# Sheet_1_2022-03-11.net
KiCad netlist of a schematic drawn in Altium Designer
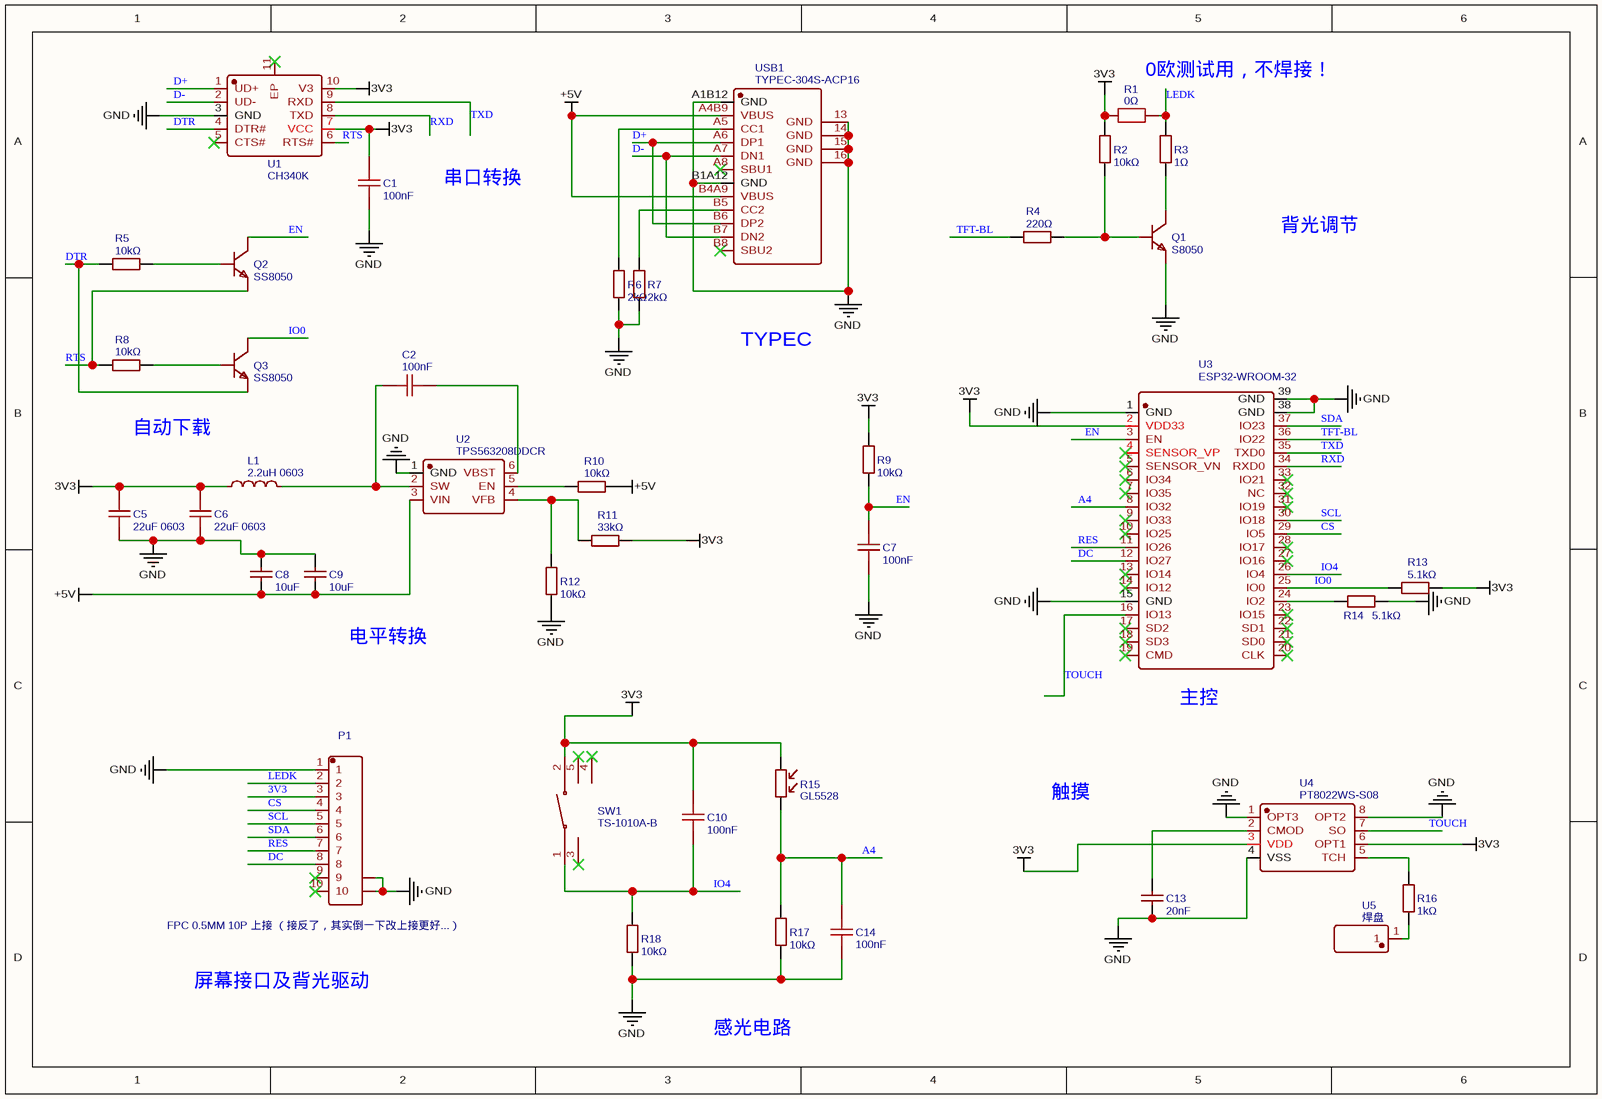
[diagram p0: Sheet_1_2022-03-11.schdoc]

(export (version "E")
  (design (tool "Eeschema 10.0.6"))
  (components
    (comp (ref "C1")
      (value "100nF")
      (fields
        (field (name "BOM_SUPPLIER PART") "C307331")
        (field (name "BOM_MANUFACTURER PART") "CL05B104KB54PNC")
        (field (name "CONTRIBUTOR") "LCSC")
      )
      (libsource (lib "altium-import") (part "root_1_100nF_"))
    )
    (comp (ref "C2")
      (value "100nF")
      (fields
        (field (name "BOM_SUPPLIER PART") "C307331")
        (field (name "BOM_MANUFACTURER PART") "CL05B104KB54PNC")
        (field (name "CONTRIBUTOR") "LCSC")
      )
      (libsource (lib "altium-import") (part "root_2_100nF_"))
    )
    (comp (ref "C5")
      (value "22uF 0603")
      (fields (field (name "CONTRIBUTOR") "LCEDA_Lib"))
      (libsource (lib "altium-import") (part "root_1_22uF 0603_"))
    )
    (comp (ref "C6")
      (value "22uF 0603")
      (fields (field (name "CONTRIBUTOR") "LCEDA_Lib"))
      (libsource (lib "altium-import") (part "root_1_22uF 0603_"))
    )
    (comp (ref "C7")
      (value "100nF")
      (fields
        (field (name "BOM_SUPPLIER PART") "C307331")
        (field (name "BOM_MANUFACTURER PART") "CL05B104KB54PNC")
        (field (name "CONTRIBUTOR") "LCSC")
      )
      (libsource (lib "altium-import") (part "root_1_100nF_"))
    )
    (comp (ref "C8")
      (value "10uF")
      (fields
        (field (name "BOM_MANUFACTURER PART") "CL05A106MQ5NUNC")
        (field (name "BOM_SUPPLIER PART") "C15525")
      )
      (libsource (lib "altium-import") (part "root_1_10uF_"))
    )
    (comp (ref "C9")
      (value "10uF")
      (fields
        (field (name "BOM_MANUFACTURER PART") "CL05A106MQ5NUNC")
        (field (name "BOM_SUPPLIER PART") "C15525")
      )
      (libsource (lib "altium-import") (part "root_1_10uF_"))
    )
    (comp (ref "C10")
      (value "100nF")
      (fields
        (field (name "BOM_SUPPLIER PART") "C307331")
        (field (name "BOM_MANUFACTURER PART") "CL05B104KB54PNC")
        (field (name "CONTRIBUTOR") "LCSC")
      )
      (libsource (lib "altium-import") (part "root_1_100nF_"))
    )
    (comp (ref "C13")
      (value "20nF")
      (fields
        (field (name "BOM_MANUFACTURER PART") "0402F203M500NT")
        (field (name "BOM_SUPPLIER PART") "C79469")
      )
      (libsource (lib "altium-import") (part "root_3_20nF_"))
    )
    (comp (ref "C14")
      (value "100nF")
      (fields
        (field (name "BOM_SUPPLIER PART") "C307331")
        (field (name "BOM_MANUFACTURER PART") "CL05B104KB54PNC")
        (field (name "CONTRIBUTOR") "LCSC")
      )
      (libsource (lib "altium-import") (part "root_1_100nF_"))
    )
    (comp (ref "L1")
      (value "2.2uH 0603")
      (fields (field (name "CONTRIBUTOR") "LCEDA_Lib"))
      (libsource (lib "altium-import") (part "root_0_2.2uH 0603_"))
    )
    (comp (ref "P1")
      (value "FPC 0.5MM 10P 上接 （接反了，其实倒一下改上接更好...）")
      (fields
        (field (name "BOM_MANUFACTURER PART") "FPC 0.5MM 10P Pull type H2.0mm Pick up")
        (field (name "BOM_SUPPLIER PART") "C11085")
      )
      (libsource (lib "altium-import") (part "root_0_FPC 0.5MM 10P 上接 （接反了，其实倒一下改上接更好...）_"))
    )
    (comp (ref "Q1")
      (value "S8050")
      (fields (field (name "BOM_SUPPLIER PART") "C916390") (field (name "CONTRIBUTOR") "LCSC"))
      (libsource (lib "altium-import") (part "root_0_S8050_"))
    )
    (comp (ref "Q2")
      (value "SS8050")
      (fields (field (name "BOM_SUPPLIER PART") "C2688219") (field (name "CONTRIBUTOR") "LCSC"))
      (libsource (lib "altium-import") (part "root_0_SS8050_"))
    )
    (comp (ref "Q3")
      (value "SS8050")
      (fields (field (name "BOM_SUPPLIER PART") "C2688219") (field (name "CONTRIBUTOR") "LCSC"))
      (libsource (lib "altium-import") (part "root_0_SS8050_"))
    )
    (comp (ref "R1")
      (value "0Ω")
      (fields (field (name "CONTRIBUTOR") "LCEDA_Lib"))
      (libsource (lib "altium-import") (part "root_0_0Ω_"))
    )
    (comp (ref "R2")
      (value "10kΩ")
      (fields
        (field (name "BOM_MANUFACTURER PART") "0402WGF1002TCE")
        (field (name "BOM_SUPPLIER PART") "C25744")
      )
      (libsource (lib "altium-import") (part "root_1_10kΩ_"))
    )
    (comp (ref "R3")
      (value "1Ω")
      (fields
        (field (name "BOM_MANUFACTURER PART") "0402WGF100KTCE")
        (field (name "BOM_SUPPLIER PART") "C25086")
      )
      (libsource (lib "altium-import") (part "root_1_1Ω_"))
    )
    (comp (ref "R4")
      (value "220Ω")
      (fields
        (field (name "BOM_MANUFACTURER PART") "0603WAF2200T5E")
        (field (name "BOM_SUPPLIER PART") "C22962")
      )
      (libsource (lib "altium-import") (part "root_2_220Ω_"))
    )
    (comp (ref "R5")
      (value "10kΩ")
      (fields
        (field (name "BOM_MANUFACTURER PART") "0402WGF1002TCE")
        (field (name "BOM_SUPPLIER PART") "C25744")
      )
      (libsource (lib "altium-import") (part "root_0_10kΩ_"))
    )
    (comp (ref "R6")
      (value "2kΩ")
      (fields
        (field (name "BOM_MANUFACTURER PART") "0402WGF2001TCE")
        (field (name "BOM_SUPPLIER PART") "C4109")
      )
      (libsource (lib "altium-import") (part "root_1_2kΩ_"))
    )
    (comp (ref "R7")
      (value "2kΩ")
      (fields
        (field (name "BOM_MANUFACTURER PART") "0402WGF2001TCE")
        (field (name "BOM_SUPPLIER PART") "C4109")
      )
      (libsource (lib "altium-import") (part "root_1_2kΩ_"))
    )
    (comp (ref "R8")
      (value "10kΩ")
      (fields
        (field (name "BOM_MANUFACTURER PART") "0402WGF1002TCE")
        (field (name "BOM_SUPPLIER PART") "C25744")
      )
      (libsource (lib "altium-import") (part "root_2_10kΩ_"))
    )
    (comp (ref "R9")
      (value "10kΩ")
      (fields
        (field (name "BOM_MANUFACTURER PART") "0402WGF1002TCE")
        (field (name "BOM_SUPPLIER PART") "C25744")
      )
      (libsource (lib "altium-import") (part "root_1_10kΩ_"))
    )
    (comp (ref "R10")
      (value "10kΩ")
      (fields
        (field (name "BOM_MANUFACTURER PART") "0402WGF1002TCE")
        (field (name "BOM_SUPPLIER PART") "C25744")
      )
      (libsource (lib "altium-import") (part "root_0_10kΩ_"))
    )
    (comp (ref "R11")
      (value "33kΩ")
      (fields
        (field (name "BOM_MANUFACTURER PART") "0402WGF3302TCE")
        (field (name "BOM_SUPPLIER PART") "C25779")
      )
      (libsource (lib "altium-import") (part "root_0_33kΩ_"))
    )
    (comp (ref "R12")
      (value "10kΩ")
      (fields
        (field (name "BOM_MANUFACTURER PART") "0402WGF1002TCE")
        (field (name "BOM_SUPPLIER PART") "C25744")
      )
      (libsource (lib "altium-import") (part "root_1_10kΩ_"))
    )
    (comp (ref "R13")
      (value "5.1kΩ")
      (fields
        (field (name "BOM_MANUFACTURER PART") "0402WGF5101TCE")
        (field (name "BOM_SUPPLIER PART") "C25905")
      )
      (libsource (lib "altium-import") (part "root_0_5.1kΩ_"))
    )
    (comp (ref "R14")
      (value "5.1kΩ")
      (fields
        (field (name "BOM_MANUFACTURER PART") "0402WGF5101TCE")
        (field (name "BOM_SUPPLIER PART") "C25905")
      )
      (libsource (lib "altium-import") (part "root_0_5.1kΩ_"))
    )
    (comp (ref "R15")
      (value "GL5528")
      (fields (field (name "BOM_SUPPLIER PART") "C125627"))
      (libsource (lib "altium-import") (part "root_3_GL5528_"))
    )
    (comp (ref "R16")
      (value "1kΩ")
      (fields
        (field (name "BOM_MANUFACTURER PART") "0402WGF1001TCE")
        (field (name "BOM_SUPPLIER PART") "C11702")
      )
      (libsource (lib "altium-import") (part "root_1_1kΩ_"))
    )
    (comp (ref "R17")
      (value "10kΩ")
      (fields
        (field (name "BOM_MANUFACTURER PART") "0402WGF1002TCE")
        (field (name "BOM_SUPPLIER PART") "C25744")
      )
      (libsource (lib "altium-import") (part "root_1_10kΩ_"))
    )
    (comp (ref "R18")
      (value "10kΩ")
      (fields
        (field (name "BOM_MANUFACTURER PART") "0402WGF1002TCE")
        (field (name "BOM_SUPPLIER PART") "C25744")
      )
      (libsource (lib "altium-import") (part "root_1_10kΩ_"))
    )
    (comp (ref "SW1")
      (value "TS-1010A-B")
      (fields (field (name "BOM_SUPPLIER PART") "C381059") (field (name "CONTRIBUTOR") "LCSC"))
      (libsource (lib "altium-import") (part "root_1_TS-1010A-B_"))
    )
    (comp (ref "U1")
      (value "CH340K")
      (fields (field (name "BOM_SUPPLIER PART") "C968586") (field (name "CONTRIBUTOR") "LCSC"))
      (libsource (lib "altium-import") (part "root_0_CH340K_"))
    )
    (comp (ref "U2")
      (value "TPS563208DDCR")
      (fields (field (name "BOM_SUPPLIER PART") "C468250") (field (name "CONTRIBUTOR") "LCSC"))
      (libsource (lib "altium-import") (part "root_0_TPS563208DDCR_"))
    )
    (comp (ref "U3")
      (value "ESP32-WROOM-32")
      (fields (field (name "BOM_SUPPLIER PART") "C503587") (field (name "CONTRIBUTOR") "LCSC"))
      (libsource (lib "altium-import") (part "root_0_ESP32-WROOM-32_"))
    )
    (comp (ref "U4")
      (value "PT8022WS-S08")
      (fields (field (name "BOM_SUPPLIER PART") "C2936083") (field (name "CONTRIBUTOR") "LCSC"))
      (libsource (lib "altium-import") (part "root_0_PT8022WS-S08_"))
    )
    (comp (ref "U5")
      (value "焊盘")
      (fields (field (name "BOM_MANUFACTURER PART") "New SchematicLib") (field (name "CONTRIBUTOR") "Kisro"))
      (libsource (lib "altium-import") (part "root_2_焊盘_"))
    )
    (comp (ref "USB1")
      (value "TYPEC-304S-ACP16")
      (fields (field (name "BOM_SUPPLIER PART") "C720630") (field (name "CONTRIBUTOR") "LCSC"))
      (libsource (lib "altium-import") (part "root_0_TYPEC-304S-ACP16_"))
    )
  )
  (nets
    (net (code "1") (name "+5V") (class "Default")
      (node (ref "C8") (pin "1") (pinfunction "1_1") (pintype "passive"))
      (node (ref "C9") (pin "1") (pinfunction "1_1") (pintype "passive"))
      (node (ref "R10") (pin "2") (pinfunction "2_2") (pintype "passive"))
      (node (ref "U2") (pin "3") (pinfunction "VIN_3") (pintype "passive"))
      (node (ref "USB1") (pin "A4B9") (pinfunction "VBUS_A4B9") (pintype "passive"))
      (node (ref "USB1") (pin "B4A9") (pinfunction "VBUS_B4A9") (pintype "passive"))
    )
    (net (code "2") (name "/A4") (class "Default")
      (node (ref "C14") (pin "2") (pinfunction "2_2") (pintype "passive"))
      (node (ref "R15") (pin "2") (pinfunction "2_2") (pintype "passive"))
      (node (ref "R17") (pin "2") (pinfunction "2_2") (pintype "passive"))
      (node (ref "U3") (pin "8") (pinfunction "IO32_8") (pintype "passive"))
    )
    (net (code "3") (name "/CS") (class "Default")
      (node (ref "P1") (pin "4") (pinfunction "4_4") (pintype "passive"))
      (node (ref "U3") (pin "29") (pinfunction "IO5_29") (pintype "passive"))
    )
    (net (code "4") (name "/D+") (class "Default")
      (node (ref "U1") (pin "1") (pinfunction "UD+_1") (pintype "passive"))
      (node (ref "USB1") (pin "A6") (pinfunction "DP1_A6") (pintype "passive"))
      (node (ref "USB1") (pin "B6") (pinfunction "DP2_B6") (pintype "passive"))
    )
    (net (code "5") (name "/D-") (class "Default")
      (node (ref "U1") (pin "2") (pinfunction "UD-_2") (pintype "passive"))
      (node (ref "USB1") (pin "A7") (pinfunction "DN1_A7") (pintype "passive"))
      (node (ref "USB1") (pin "B7") (pinfunction "DN2_B7") (pintype "passive"))
    )
    (net (code "6") (name "/DC") (class "Default")
      (node (ref "P1") (pin "8") (pinfunction "8_8") (pintype "passive"))
      (node (ref "U3") (pin "12") (pinfunction "IO27_12") (pintype "passive"))
    )
    (net (code "7") (name "/DTR") (class "Default")
      (node (ref "Q3") (pin "2") (pinfunction "E_2") (pintype "passive"))
      (node (ref "R5") (pin "1") (pinfunction "1_1") (pintype "passive"))
      (node (ref "U1") (pin "4") (pinfunction "DTR#_4") (pintype "passive"))
    )
    (net (code "8") (name "/EN") (class "Default")
      (node (ref "C7") (pin "2") (pinfunction "2_2") (pintype "passive"))
      (node (ref "Q2") (pin "3") (pinfunction "C_3") (pintype "passive"))
      (node (ref "R9") (pin "1") (pinfunction "1_1") (pintype "passive"))
      (node (ref "U3") (pin "3") (pinfunction "EN_3") (pintype "passive"))
    )
    (net (code "9") (name "/IO0") (class "Default")
      (node (ref "Q3") (pin "3") (pinfunction "C_3") (pintype "passive"))
      (node (ref "R13") (pin "1") (pinfunction "1_1") (pintype "passive"))
      (node (ref "U3") (pin "25") (pinfunction "IO0_25") (pintype "passive"))
    )
    (net (code "10") (name "/IO4") (class "Default")
      (node (ref "C10") (pin "1") (pinfunction "1_1") (pintype "passive"))
      (node (ref "R18") (pin "2") (pinfunction "2_2") (pintype "passive"))
      (node (ref "SW1") (pin "1") (pinfunction "1_1") (pintype "passive"))
      (node (ref "U3") (pin "26") (pinfunction "IO4_26") (pintype "passive"))
    )
    (net (code "11") (name "/LEDK") (class "Default")
      (node (ref "P1") (pin "2") (pinfunction "2_2") (pintype "passive"))
      (node (ref "R1") (pin "2") (pinfunction "2_2") (pintype "passive"))
      (node (ref "R3") (pin "2") (pinfunction "2_2") (pintype "passive"))
    )
    (net (code "12") (name "/RES") (class "Default")
      (node (ref "P1") (pin "7") (pinfunction "7_7") (pintype "passive"))
      (node (ref "U3") (pin "11") (pinfunction "IO26_11") (pintype "passive"))
    )
    (net (code "13") (name "/RTS") (class "Default")
      (node (ref "Q2") (pin "2") (pinfunction "E_2") (pintype "passive"))
      (node (ref "R8") (pin "2") (pinfunction "2_2") (pintype "passive"))
      (node (ref "U1") (pin "6") (pinfunction "RTS#_6") (pintype "passive"))
    )
    (net (code "14") (name "/RXD") (class "Default")
      (node (ref "U1") (pin "8") (pinfunction "TXD_8") (pintype "passive"))
      (node (ref "U3") (pin "34") (pinfunction "RXD0_34") (pintype "passive"))
    )
    (net (code "15") (name "/SCL") (class "Default")
      (node (ref "P1") (pin "5") (pinfunction "5_5") (pintype "passive"))
      (node (ref "U3") (pin "30") (pinfunction "IO18_30") (pintype "passive"))
    )
    (net (code "16") (name "/SDA") (class "Default")
      (node (ref "P1") (pin "6") (pinfunction "6_6") (pintype "passive"))
      (node (ref "U3") (pin "37") (pinfunction "IO23_37") (pintype "passive"))
    )
    (net (code "17") (name "/TFT-BL") (class "Default")
      (node (ref "R4") (pin "2") (pinfunction "2_2") (pintype "passive"))
      (node (ref "U3") (pin "36") (pinfunction "IO22_36") (pintype "passive"))
    )
    (net (code "18") (name "/TOUCH") (class "Default")
      (node (ref "U3") (pin "16") (pinfunction "IO13_16") (pintype "passive"))
      (node (ref "U4") (pin "7") (pinfunction "SO_7") (pintype "passive"))
    )
    (net (code "19") (name "/TXD") (class "Default")
      (node (ref "U1") (pin "9") (pinfunction "RXD_9") (pintype "passive"))
      (node (ref "U3") (pin "35") (pinfunction "TXD0_35") (pintype "passive"))
    )
    (net (code "20") (name "3V3") (class "Default")
      (node (ref "C1") (pin "2") (pinfunction "2_2") (pintype "passive"))
      (node (ref "C10") (pin "2") (pinfunction "2_2") (pintype "passive"))
      (node (ref "C5") (pin "2") (pinfunction "2_2") (pintype "passive"))
      (node (ref "C6") (pin "2") (pinfunction "2_2") (pintype "passive"))
      (node (ref "L1") (pin "1") (pinfunction "1_1") (pintype "passive"))
      (node (ref "P1") (pin "3") (pinfunction "3_3") (pintype "passive"))
      (node (ref "R1") (pin "1") (pinfunction "1_1") (pintype "passive"))
      (node (ref "R11") (pin "2") (pinfunction "2_2") (pintype "passive"))
      (node (ref "R13") (pin "2") (pinfunction "2_2") (pintype "passive"))
      (node (ref "R15") (pin "1") (pinfunction "1_1") (pintype "passive"))
      (node (ref "R2") (pin "2") (pinfunction "2_2") (pintype "passive"))
      (node (ref "R9") (pin "2") (pinfunction "2_2") (pintype "passive"))
      (node (ref "SW1") (pin "2") (pinfunction "2_2") (pintype "passive"))
      (node (ref "U1") (pin "10") (pinfunction "V3_10") (pintype "passive"))
      (node (ref "U1") (pin "7") (pinfunction "VCC_7") (pintype "passive"))
      (node (ref "U3") (pin "2") (pinfunction "VDD33_2") (pintype "passive"))
      (node (ref "U4") (pin "3") (pinfunction "VDD_3") (pintype "passive"))
      (node (ref "U4") (pin "6") (pinfunction "OPT1_6") (pintype "passive"))
    )
    (net (code "21") (name "GND") (class "Default")
      (node (ref "C1") (pin "1") (pinfunction "1_1") (pintype "passive"))
      (node (ref "C13") (pin "2") (pinfunction "2_2") (pintype "passive"))
      (node (ref "C14") (pin "1") (pinfunction "1_1") (pintype "passive"))
      (node (ref "C5") (pin "1") (pinfunction "1_1") (pintype "passive"))
      (node (ref "C6") (pin "1") (pinfunction "1_1") (pintype "passive"))
      (node (ref "C7") (pin "1") (pinfunction "1_1") (pintype "passive"))
      (node (ref "C8") (pin "2") (pinfunction "2_2") (pintype "passive"))
      (node (ref "C9") (pin "2") (pinfunction "2_2") (pintype "passive"))
      (node (ref "P1") (pin "1") (pinfunction "1_1") (pintype "passive"))
      (node (ref "P1") (pin "11") (pinfunction "11_11") (pintype "passive"))
      (node (ref "P1") (pin "12") (pinfunction "12_12") (pintype "passive"))
      (node (ref "Q1") (pin "2") (pinfunction "E_2") (pintype "passive"))
      (node (ref "R12") (pin "1") (pinfunction "1_1") (pintype "passive"))
      (node (ref "R14") (pin "2") (pinfunction "2_2") (pintype "passive"))
      (node (ref "R17") (pin "1") (pinfunction "1_1") (pintype "passive"))
      (node (ref "R18") (pin "1") (pinfunction "1_1") (pintype "passive"))
      (node (ref "R6") (pin "1") (pinfunction "1_1") (pintype "passive"))
      (node (ref "R7") (pin "1") (pinfunction "1_1") (pintype "passive"))
      (node (ref "U1") (pin "3") (pinfunction "GND_3") (pintype "passive"))
      (node (ref "U2") (pin "1") (pinfunction "GND_1") (pintype "passive"))
      (node (ref "U3") (pin "1") (pinfunction "GND_1") (pintype "passive"))
      (node (ref "U3") (pin "15") (pinfunction "GND_15") (pintype "passive"))
      (node (ref "U3") (pin "38") (pinfunction "GND_38") (pintype "passive"))
      (node (ref "U3") (pin "39") (pinfunction "GND_39") (pintype "passive"))
      (node (ref "U4") (pin "1") (pinfunction "OPT3_1") (pintype "passive"))
      (node (ref "U4") (pin "4") (pinfunction "VSS_4") (pintype "passive"))
      (node (ref "U4") (pin "8") (pinfunction "OPT2_8") (pintype "passive"))
      (node (ref "USB1") (pin "13") (pinfunction "GND_13") (pintype "passive"))
      (node (ref "USB1") (pin "14") (pinfunction "GND_14") (pintype "passive"))
      (node (ref "USB1") (pin "15") (pinfunction "GND_15") (pintype "passive"))
      (node (ref "USB1") (pin "16") (pinfunction "GND_16") (pintype "passive"))
      (node (ref "USB1") (pin "A1B12") (pinfunction "GND_A1B12") (pintype "passive"))
      (node (ref "USB1") (pin "B1A12") (pinfunction "GND_B1A12") (pintype "passive"))
    )
    (net (code "22") (name "Net-(Q1-B)") (class "Default")
      (node (ref "Q1") (pin "1") (pinfunction "B_1") (pintype "passive"))
      (node (ref "R2") (pin "1") (pinfunction "1_1") (pintype "passive"))
      (node (ref "R4") (pin "1") (pinfunction "1_1") (pintype "passive"))
    )
    (net (code "23") (name "Net-(Q1-C)") (class "Default")
      (node (ref "Q1") (pin "3") (pinfunction "C_3") (pintype "passive"))
      (node (ref "R3") (pin "1") (pinfunction "1_1") (pintype "passive"))
    )
    (net (code "24") (name "Net-(Q2-B)") (class "Default")
      (node (ref "Q2") (pin "1") (pinfunction "B_1") (pintype "passive"))
      (node (ref "R5") (pin "2") (pinfunction "2_2") (pintype "passive"))
    )
    (net (code "25") (name "Net-(Q3-B)") (class "Default")
      (node (ref "Q3") (pin "1") (pinfunction "B_1") (pintype "passive"))
      (node (ref "R8") (pin "1") (pinfunction "1_1") (pintype "passive"))
    )
    (net (code "26") (name "Net-(R16-Pad1)") (class "Default")
      (node (ref "R16") (pin "1") (pinfunction "1_1") (pintype "passive"))
      (node (ref "U5") (pin "1") (pinfunction "1_1") (pintype "passive"))
    )
    (net (code "27") (name "Net-(U2-EN)") (class "Default")
      (node (ref "R10") (pin "1") (pinfunction "1_1") (pintype "passive"))
      (node (ref "U2") (pin "5") (pinfunction "EN_5") (pintype "passive"))
    )
    (net (code "28") (name "Net-(U2-SW)") (class "Default")
      (node (ref "C2") (pin "2") (pinfunction "2_2") (pintype "passive"))
      (node (ref "L1") (pin "2") (pinfunction "2_2") (pintype "passive"))
      (node (ref "U2") (pin "2") (pinfunction "SW_2") (pintype "passive"))
    )
    (net (code "29") (name "Net-(U2-VBST)") (class "Default")
      (node (ref "C2") (pin "1") (pinfunction "1_1") (pintype "passive"))
      (node (ref "U2") (pin "6") (pinfunction "VBST_6") (pintype "passive"))
    )
    (net (code "30") (name "Net-(U2-VFB)") (class "Default")
      (node (ref "R11") (pin "1") (pinfunction "1_1") (pintype "passive"))
      (node (ref "R12") (pin "2") (pinfunction "2_2") (pintype "passive"))
      (node (ref "U2") (pin "4") (pinfunction "VFB_4") (pintype "passive"))
    )
    (net (code "31") (name "Net-(U3-IO2)") (class "Default")
      (node (ref "R14") (pin "1") (pinfunction "1_1") (pintype "passive"))
      (node (ref "U3") (pin "24") (pinfunction "IO2_24") (pintype "passive"))
    )
    (net (code "32") (name "Net-(U4-CMOD)") (class "Default")
      (node (ref "C13") (pin "1") (pinfunction "1_1") (pintype "passive"))
      (node (ref "U4") (pin "2") (pinfunction "CMOD_2") (pintype "passive"))
    )
    (net (code "33") (name "Net-(U4-TCH)") (class "Default")
      (node (ref "R16") (pin "2") (pinfunction "2_2") (pintype "passive"))
      (node (ref "U4") (pin "5") (pinfunction "TCH_5") (pintype "passive"))
    )
    (net (code "34") (name "Net-(USB1-CC1)") (class "Default")
      (node (ref "R6") (pin "2") (pinfunction "2_2") (pintype "passive"))
      (node (ref "USB1") (pin "A5") (pinfunction "CC1_A5") (pintype "passive"))
    )
    (net (code "35") (name "Net-(USB1-CC2)") (class "Default")
      (node (ref "R7") (pin "2") (pinfunction "2_2") (pintype "passive"))
      (node (ref "USB1") (pin "B5") (pinfunction "CC2_B5") (pintype "passive"))
    )
    (net (code "36") (name "unconnected-(P1-Pad9)") (class "Default")
      (node (ref "P1") (pin "9") (pinfunction "9_9") (pintype "passive+no_connect"))
    )
    (net (code "37") (name "unconnected-(P1-Pad10)") (class "Default")
      (node (ref "P1") (pin "10") (pinfunction "10_10") (pintype "passive+no_connect"))
    )
    (net (code "38") (name "unconnected-(SW1-Pad3)") (class "Default")
      (node (ref "SW1") (pin "3") (pinfunction "3_3") (pintype "passive+no_connect"))
    )
    (net (code "39") (name "unconnected-(SW1-Pad4)") (class "Default")
      (node (ref "SW1") (pin "4") (pinfunction "4_4") (pintype "passive+no_connect"))
    )
    (net (code "40") (name "unconnected-(SW1-Pad5)") (class "Default")
      (node (ref "SW1") (pin "5") (pinfunction "5_5") (pintype "passive+no_connect"))
    )
    (net (code "41") (name "unconnected-(U1-CTS#-Pad5)") (class "Default")
      (node (ref "U1") (pin "5") (pinfunction "CTS#_5") (pintype "passive+no_connect"))
    )
    (net (code "42") (name "unconnected-(U1-EP-Pad11)") (class "Default")
      (node (ref "U1") (pin "11") (pinfunction "EP_11") (pintype "passive+no_connect"))
    )
    (net (code "43") (name "unconnected-(U3-CLK-Pad20)") (class "Default")
      (node (ref "U3") (pin "20") (pinfunction "CLK_20") (pintype "passive+no_connect"))
    )
    (net (code "44") (name "unconnected-(U3-CMD-Pad19)") (class "Default")
      (node (ref "U3") (pin "19") (pinfunction "CMD_19") (pintype "passive+no_connect"))
    )
    (net (code "45") (name "unconnected-(U3-IO12-Pad14)") (class "Default")
      (node (ref "U3") (pin "14") (pinfunction "IO12_14") (pintype "passive+no_connect"))
    )
    (net (code "46") (name "unconnected-(U3-IO14-Pad13)") (class "Default")
      (node (ref "U3") (pin "13") (pinfunction "IO14_13") (pintype "passive+no_connect"))
    )
    (net (code "47") (name "unconnected-(U3-IO15-Pad23)") (class "Default")
      (node (ref "U3") (pin "23") (pinfunction "IO15_23") (pintype "passive+no_connect"))
    )
    (net (code "48") (name "unconnected-(U3-IO16-Pad27)") (class "Default")
      (node (ref "U3") (pin "27") (pinfunction "IO16_27") (pintype "passive+no_connect"))
    )
    (net (code "49") (name "unconnected-(U3-IO17-Pad28)") (class "Default")
      (node (ref "U3") (pin "28") (pinfunction "IO17_28") (pintype "passive+no_connect"))
    )
    (net (code "50") (name "unconnected-(U3-IO19-Pad31)") (class "Default")
      (node (ref "U3") (pin "31") (pinfunction "IO19_31") (pintype "passive+no_connect"))
    )
    (net (code "51") (name "unconnected-(U3-IO21-Pad33)") (class "Default")
      (node (ref "U3") (pin "33") (pinfunction "IO21_33") (pintype "passive+no_connect"))
    )
    (net (code "52") (name "unconnected-(U3-IO25-Pad10)") (class "Default")
      (node (ref "U3") (pin "10") (pinfunction "IO25_10") (pintype "passive+no_connect"))
    )
    (net (code "53") (name "unconnected-(U3-IO33-Pad9)") (class "Default")
      (node (ref "U3") (pin "9") (pinfunction "IO33_9") (pintype "passive+no_connect"))
    )
    (net (code "54") (name "unconnected-(U3-IO34-Pad6)") (class "Default")
      (node (ref "U3") (pin "6") (pinfunction "IO34_6") (pintype "passive+no_connect"))
    )
    (net (code "55") (name "unconnected-(U3-IO35-Pad7)") (class "Default")
      (node (ref "U3") (pin "7") (pinfunction "IO35_7") (pintype "passive+no_connect"))
    )
    (net (code "56") (name "unconnected-(U3-NC-Pad32)") (class "Default")
      (node (ref "U3") (pin "32") (pinfunction "NC_32") (pintype "passive+no_connect"))
    )
    (net (code "57") (name "unconnected-(U3-SD0-Pad21)") (class "Default")
      (node (ref "U3") (pin "21") (pinfunction "SD0_21") (pintype "passive+no_connect"))
    )
    (net (code "58") (name "unconnected-(U3-SD1-Pad22)") (class "Default")
      (node (ref "U3") (pin "22") (pinfunction "SD1_22") (pintype "passive+no_connect"))
    )
    (net (code "59") (name "unconnected-(U3-SD2-Pad17)") (class "Default")
      (node (ref "U3") (pin "17") (pinfunction "SD2_17") (pintype "passive+no_connect"))
    )
    (net (code "60") (name "unconnected-(U3-SD3-Pad18)") (class "Default")
      (node (ref "U3") (pin "18") (pinfunction "SD3_18") (pintype "passive+no_connect"))
    )
    (net (code "61") (name "unconnected-(U3-SENSOR_VN-Pad5)") (class "Default")
      (node (ref "U3") (pin "5") (pinfunction "SENSOR_VN_5") (pintype "passive+no_connect"))
    )
    (net (code "62") (name "unconnected-(U3-SENSOR_VP-Pad4)") (class "Default")
      (node (ref "U3") (pin "4") (pinfunction "SENSOR_VP_4") (pintype "passive+no_connect"))
    )
    (net (code "63") (name "unconnected-(USB1-SBU1-PadA8)") (class "Default")
      (node (ref "USB1") (pin "A8") (pinfunction "SBU1_A8") (pintype "passive+no_connect"))
    )
    (net (code "64") (name "unconnected-(USB1-SBU2-PadB8)") (class "Default")
      (node (ref "USB1") (pin "B8") (pinfunction "SBU2_B8") (pintype "passive+no_connect"))
    )
  )
)
